# ZIF_HIZ_and_Converter.net
KiCad netlist of a schematic drawn in Altium Designer
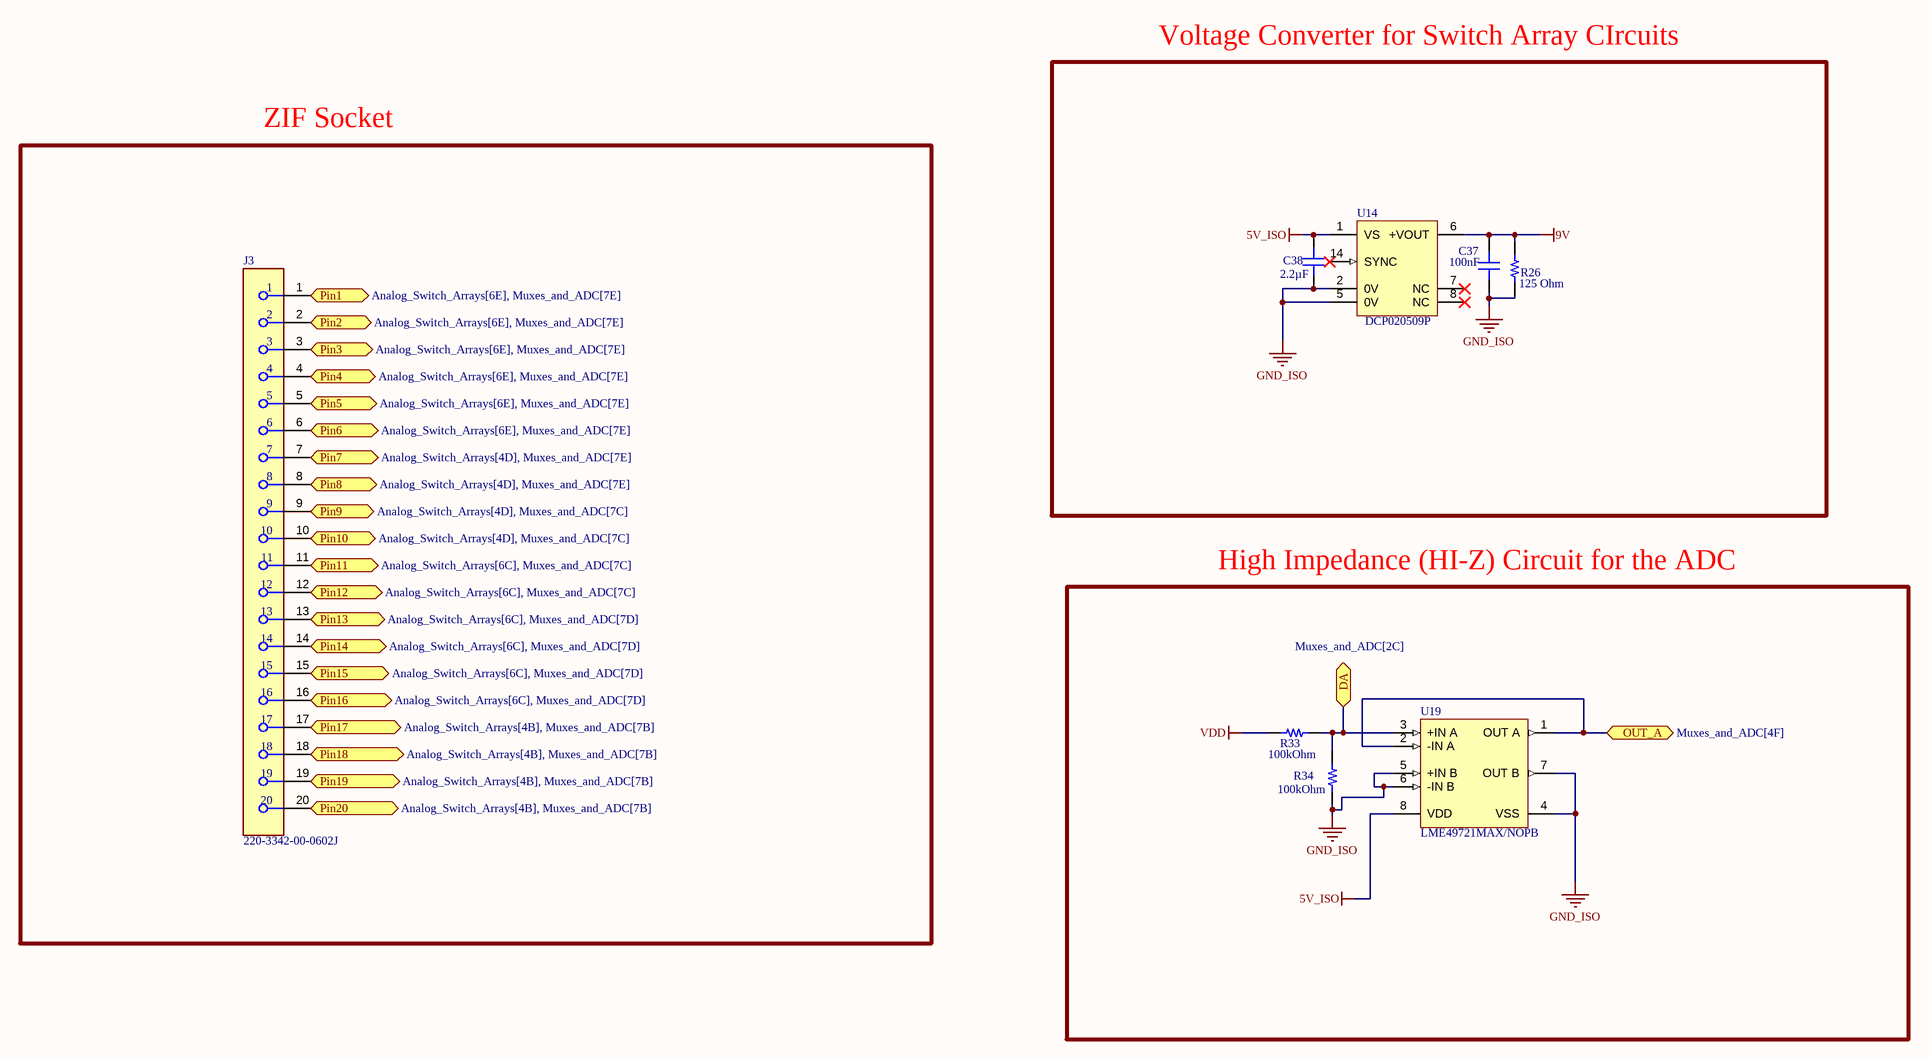
[diagram p0: ZIF_HIZ_and_Converter.SchDoc]

(export (version "E")
  (design (tool "Eeschema 10.0.6"))
  (components
    (comp (ref "C37")
      (value "100nF")
      (footprint "CAP 1206_3216 - 0.8MM")
      (description "CAP CER 1206 0.1F 16V ULTRA STAB")
      (fields (field (name "PART NUMBER") "C1206X104G4HAC7800"))
      (libsource (lib "University of Massachusetts Lowell") (part "CAPACITOR"))
    )
    (comp (ref "C38")
      (value "2.2µF")
      (footprint "CAP 1206_3216 - 0.8MM")
      (description "CAP CER 2.2UF 25V Y5V 1206")
      (fields (field (name "PART NUMBER") "CC1206ZRY5V8BB225"))
      (libsource (lib "University of Massachusetts Lowell") (part "CAPACITOR"))
    )
    (comp (ref "J3")
      (value "220-3342-00-0602J")
      (footprint "FP-220-3342-00-0602J-0")
      (description "CONN IC DIP SOCKET ZIF 20POS GLD")
      (fields
        (field (name "MANUFACTURER") "3M")
        (field (name "OCTOPART") "https://octopart.com/220-3342-00-0602j-3m-108647")
      )
      (libsource (lib "Altium Content Vault") (part "dba14e038e6f7492952b7f1e871f183"))
    )
    (comp (ref "R26")
      (value "125 Ohm")
      (footprint "YAGEO RES 1206_3216")
      (description "RES SMD 125 OHM 0.1% 1/4W 1206")
      (fields (field (name "PART NUMBER") "RT1206BRD07125RL"))
      (libsource (lib "University of Massachusetts Lowell") (part "RESISTOR"))
    )
    (comp (ref "R33")
      (value "100kOhm")
      (footprint "RES 1206_3216")
      (description "RES 100K OHM 0.1% 1/4W 1206")
      (fields (field (name "PART NUMBER") "TNPW1206100KBEEA"))
      (libsource (lib "University of Massachusetts Lowell") (part "RESISTOR"))
    )
    (comp (ref "R34")
      (value "100kOhm")
      (footprint "RES 1206_3216")
      (description "RES 100K OHM 0.1% 1/4W 1206")
      (fields (field (name "PART NUMBER") "TNPW1206100KBEEA"))
      (libsource (lib "University of Massachusetts Lowell") (part "RESISTOR"))
    )
    (comp (ref "U14")
      (value "DCP020509P")
      (footprint "NVA0007A")
      (fields (field (name "MANUFACTURER") "Texas Instruments"))
      (libsource (lib "Altium Content Vault") (part "TI-DCP02XXXNVA7"))
    )
    (comp (ref "U19")
      (value "LME49721MAX/NOPB")
      (footprint "D0008A_L")
      (fields (field (name "MANUFACTURER") "Texas Instruments"))
      (libsource (lib "Altium Content Vault") (part "AMP-AUDA-LME49721-8"))
    )
  )
  (nets
    (net (code "1") (name "/DA") (class "Default")
      (node (ref "R33") (pin "2") (pinfunction "2_2") (pintype "passive"))
      (node (ref "R34") (pin "2") (pinfunction "2_2") (pintype "passive"))
      (node (ref "U19") (pin "3") (pinfunction "+IN_A_3") (pintype "input"))
    )
    (net (code "2") (name "/OUT_A") (class "Default")
      (node (ref "U19") (pin "1") (pinfunction "OUT_A_1") (pintype "output"))
      (node (ref "U19") (pin "2") (pinfunction "-IN_A_2") (pintype "input"))
    )
    (net (code "3") (name "/Pin1") (class "Default")
      (node (ref "J3") (pin "1") (pinfunction "1_1") (pintype "passive"))
    )
    (net (code "4") (name "/Pin2") (class "Default")
      (node (ref "J3") (pin "2") (pinfunction "2_2") (pintype "passive"))
    )
    (net (code "5") (name "/Pin3") (class "Default")
      (node (ref "J3") (pin "3") (pinfunction "3_3") (pintype "passive"))
    )
    (net (code "6") (name "/Pin4") (class "Default")
      (node (ref "J3") (pin "4") (pinfunction "4_4") (pintype "passive"))
    )
    (net (code "7") (name "/Pin5") (class "Default")
      (node (ref "J3") (pin "5") (pinfunction "5_5") (pintype "passive"))
    )
    (net (code "8") (name "/Pin6") (class "Default")
      (node (ref "J3") (pin "6") (pinfunction "6_6") (pintype "passive"))
    )
    (net (code "9") (name "/Pin7") (class "Default")
      (node (ref "J3") (pin "7") (pinfunction "7_7") (pintype "passive"))
    )
    (net (code "10") (name "/Pin8") (class "Default")
      (node (ref "J3") (pin "8") (pinfunction "8_8") (pintype "passive"))
    )
    (net (code "11") (name "/Pin9") (class "Default")
      (node (ref "J3") (pin "9") (pinfunction "9_9") (pintype "passive"))
    )
    (net (code "12") (name "/Pin10") (class "Default")
      (node (ref "J3") (pin "10") (pinfunction "10_10") (pintype "passive"))
    )
    (net (code "13") (name "/Pin11") (class "Default")
      (node (ref "J3") (pin "11") (pinfunction "11_11") (pintype "passive"))
    )
    (net (code "14") (name "/Pin12") (class "Default")
      (node (ref "J3") (pin "12") (pinfunction "12_12") (pintype "passive"))
    )
    (net (code "15") (name "/Pin13") (class "Default")
      (node (ref "J3") (pin "13") (pinfunction "13_13") (pintype "passive"))
    )
    (net (code "16") (name "/Pin14") (class "Default")
      (node (ref "J3") (pin "14") (pinfunction "14_14") (pintype "passive"))
    )
    (net (code "17") (name "/Pin15") (class "Default")
      (node (ref "J3") (pin "15") (pinfunction "15_15") (pintype "passive"))
    )
    (net (code "18") (name "/Pin16") (class "Default")
      (node (ref "J3") (pin "16") (pinfunction "16_16") (pintype "passive"))
    )
    (net (code "19") (name "/Pin17") (class "Default")
      (node (ref "J3") (pin "17") (pinfunction "17_17") (pintype "passive"))
    )
    (net (code "20") (name "/Pin18") (class "Default")
      (node (ref "J3") (pin "18") (pinfunction "18_18") (pintype "passive"))
    )
    (net (code "21") (name "/Pin19") (class "Default")
      (node (ref "J3") (pin "19") (pinfunction "19_19") (pintype "passive"))
    )
    (net (code "22") (name "/Pin20") (class "Default")
      (node (ref "J3") (pin "20") (pinfunction "20_20") (pintype "passive"))
    )
    (net (code "23") (name "5V_ISO") (class "Default")
      (node (ref "C38") (pin "2") (pinfunction "2_2") (pintype "passive"))
      (node (ref "U14") (pin "1") (pinfunction "VS_1") (pintype "power_in"))
      (node (ref "U19") (pin "8") (pinfunction "VDD_8") (pintype "power_in"))
    )
    (net (code "24") (name "9V") (class "Default")
      (node (ref "C37") (pin "2") (pinfunction "2_2") (pintype "passive"))
      (node (ref "R26") (pin "2") (pinfunction "2_2") (pintype "passive"))
      (node (ref "U14") (pin "6") (pinfunction "+VOUT_6") (pintype "power_in"))
    )
    (net (code "25") (name "GND_ISO") (class "Default")
      (node (ref "C37") (pin "1") (pinfunction "1_1") (pintype "passive"))
      (node (ref "C38") (pin "1") (pinfunction "1_1") (pintype "passive"))
      (node (ref "R26") (pin "1") (pinfunction "1_1") (pintype "passive"))
      (node (ref "R34") (pin "1") (pinfunction "1_1") (pintype "passive"))
      (node (ref "U14") (pin "2") (pinfunction "0V_2") (pintype "power_in"))
      (node (ref "U14") (pin "5") (pinfunction "0V_5") (pintype "power_in"))
      (node (ref "U19") (pin "4") (pinfunction "VSS_4") (pintype "power_in"))
      (node (ref "U19") (pin "5") (pinfunction "+IN_B_5") (pintype "input"))
      (node (ref "U19") (pin "6") (pinfunction "-IN_B_6") (pintype "input"))
      (node (ref "U19") (pin "7") (pinfunction "OUT_B_7") (pintype "output"))
    )
    (net (code "26") (name "VDD") (class "Default")
      (node (ref "R33") (pin "1") (pinfunction "1_1") (pintype "passive"))
    )
    (net (code "27") (name "unconnected-(U14-NC-Pad7)") (class "Default")
      (node (ref "U14") (pin "7") (pinfunction "NC_7") (pintype "passive+no_connect"))
    )
    (net (code "28") (name "unconnected-(U14-NC-Pad8)") (class "Default")
      (node (ref "U14") (pin "8") (pinfunction "NC_8") (pintype "passive+no_connect"))
    )
    (net (code "29") (name "unconnected-(U14-SYNC-Pad14)") (class "Default")
      (node (ref "U14") (pin "14") (pinfunction "SYNC_14") (pintype "input+no_connect"))
    )
  )
)
